# 4.net
KiCad netlist of a schematic drawn in EasyEDA Pro
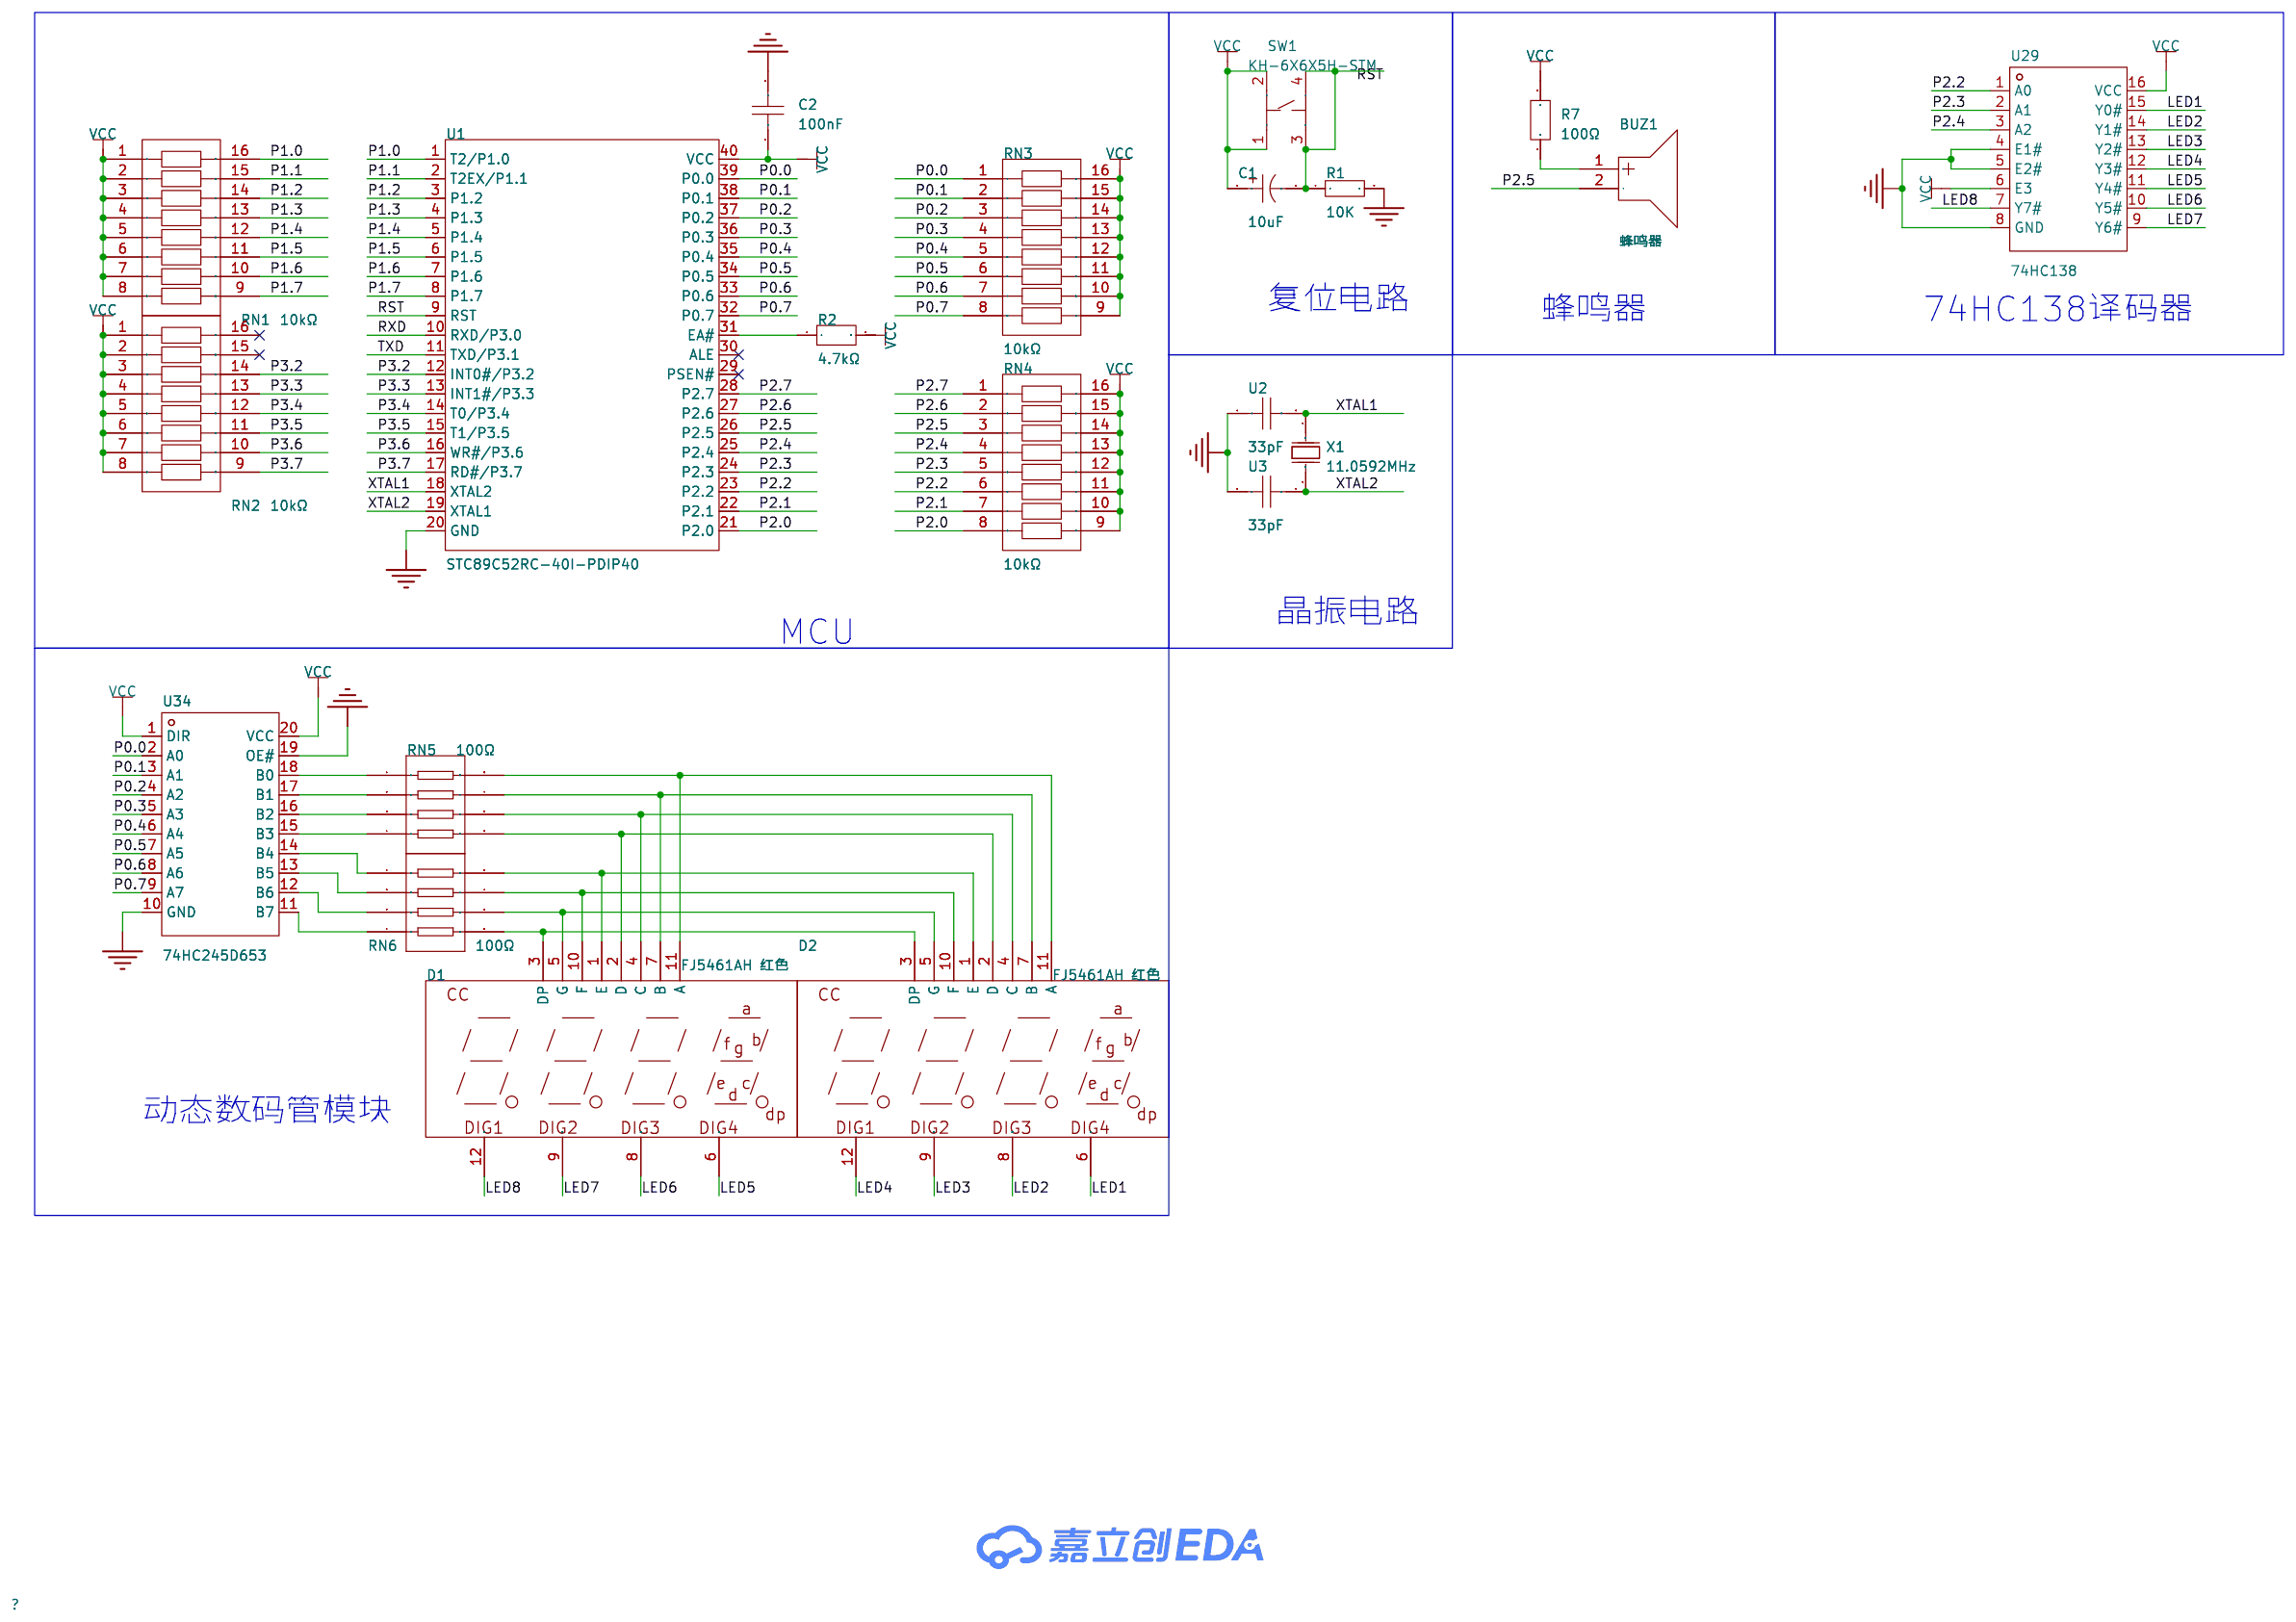
[diagram p0: schematic sheet]

(export (version "E")
  (design (tool "Eeschema 10.0.6"))
  (components
    (comp (ref "BUZ1")
      (value "蜂鸣器")
      (footprint "easyedapro:BUZ-TH_BD9.0-P5.00-D0.6-FD")
      (libsource (lib "easyedapro") (part "蜂鸣器"))
    )
    (comp (ref "C1")
      (value "10uF")
      (footprint "easyedapro:CAP-TH_BD10.0-P5.00-D0.6-FD_1")
      (description "容值:10uF;精度:±20%;额定电压:450V;纹波电流:200mA@100kHz;等效串联电阻(ESR):9Ω@100kHz;")
      (fields (field (name "Manufacturer Part") "CV100MPA16B") (field (name "Manufacturer") "TWBOR(伯鸿)"))
      (libsource (lib "easyedapro") (part "CV100MPA16B"))
    )
    (comp (ref "C2")
      (value "100nF")
      (footprint "easyedapro:C0603")
      (description "容值:100nF;精度:±10%;额定电压:25V;温度系数:X7R;")
      (fields
        (field (name "Manufacturer Part") "0603X7R104K250NT")
        (field (name "Manufacturer") "AIDE(爱迪电容)")
      )
      (libsource (lib "easyedapro") (part "0603X7R104K250NT"))
    )
    (comp (ref "D1")
      (value "FJ5461AH 红色")
      (footprint "easyedapro:LED-SEG-TH_FJ5461AH")
      (description "数码管位数:4位;功耗:-;发光颜色:红色;LED极性:共阴极;数字/字母大小(英寸):0.56;")
      (fields (field (name "Manufacturer") "志浩"))
      (libsource (lib "easyedapro") (part "FJ5461AH red"))
    )
    (comp (ref "D2")
      (value "FJ5461AH 红色")
      (footprint "easyedapro:LED-SEG-TH_FJ5461AH")
      (description "数码管位数:4位;功耗:-;发光颜色:红色;LED极性:共阴极;数字/字母大小(英寸):0.56;")
      (fields (field (name "Manufacturer") "志浩"))
      (libsource (lib "easyedapro") (part "FJ5461AH red"))
    )
    (comp (ref "R1") (value "10K") (footprint "easyedapro:R0603") (libsource (lib "easyedapro") (part "电阻")))
    (comp (ref "R2")
      (value "4.7kΩ")
      (footprint "easyedapro:R0805")
      (description "电阻类型:厚膜电阻;阻值:4.7kΩ;精度:±1%;功率:125mW;工作电压:-;温度系数:±100ppm/°C;")
      (fields
        (field (name "Manufacturer Part") "ERJ-U06F4701V")
        (field (name "Manufacturer") "PANASONIC(松下)")
      )
      (libsource (lib "easyedapro") (part "ERJ-U06F4701V"))
    )
    (comp (ref "R7")
      (value "100Ω")
      (footprint "easyedapro:R1206")
      (description "电阻类型:-;阻值:100Ω;精度:±5%;功率:250mW;工作电压:200V;")
      (fields
        (field (name "Manufacturer Part") "CQ06W4J0101T5E")
        (field (name "Manufacturer") "UNI-ROYAL(厚声)")
      )
      (libsource (lib "easyedapro") (part "CQ06W4J0101T5E"))
    )
    (comp (ref "RN1")
      (value "10kΩ")
      (footprint "easyedapro:DIP-16_L22.0-W6.7-P2.54-LS7.6-BL")
      (description "电阻器数:8;阻值:10kΩ;精度:±2%;单个元件功率:250mW;温度系数:±100ppm/°C;")
      (fields (field (name "Manufacturer Part") "4116R-1-103LF") (field (name "Manufacturer") "BOURNS"))
      (libsource (lib "easyedapro") (part "4116R-1-103LF"))
    )
    (comp (ref "RN2")
      (value "10kΩ")
      (footprint "easyedapro:DIP-16_L22.0-W6.7-P2.54-LS7.6-BL")
      (description "电阻器数:8;阻值:10kΩ;精度:±2%;单个元件功率:250mW;温度系数:±100ppm/°C;")
      (fields (field (name "Manufacturer Part") "4116R-1-103LF") (field (name "Manufacturer") "BOURNS"))
      (libsource (lib "easyedapro") (part "4116R-1-103LF"))
    )
    (comp (ref "RN3")
      (value "10kΩ")
      (footprint "easyedapro:DIP-16_L22.0-W6.7-P2.54-LS7.6-BL")
      (description "电阻器数:8;阻值:10kΩ;精度:±2%;单个元件功率:250mW;温度系数:±100ppm/°C;")
      (fields (field (name "Manufacturer Part") "4116R-1-103LF") (field (name "Manufacturer") "BOURNS"))
      (libsource (lib "easyedapro") (part "4116R-1-103LF"))
    )
    (comp (ref "RN4")
      (value "10kΩ")
      (footprint "easyedapro:DIP-16_L22.0-W6.7-P2.54-LS7.6-BL")
      (description "电阻器数:8;阻值:10kΩ;精度:±2%;单个元件功率:250mW;温度系数:±100ppm/°C;")
      (fields (field (name "Manufacturer Part") "4116R-1-103LF") (field (name "Manufacturer") "BOURNS"))
      (libsource (lib "easyedapro") (part "4116R-1-103LF"))
    )
    (comp (ref "RN5")
      (value "100Ω")
      (footprint "easyedapro:RES-ARRAY-SMD_0402-8P-L2.0-W1.0-BL")
      (description "电阻器数:4;阻值:100Ω;精度:±5%;单个元件功率:62.5mW;温度系数:±200ppm/°C;")
      (fields
        (field (name "Manufacturer Part") "4D02WGJ0101TCE")
        (field (name "Manufacturer") "UNI-ROYAL(厚声)")
      )
      (libsource (lib "easyedapro") (part "4D02WGJ0101TCE"))
    )
    (comp (ref "RN6")
      (value "100Ω")
      (footprint "easyedapro:RES-ARRAY-SMD_0402-8P-L2.0-W1.0-BL")
      (description "电阻器数:4;阻值:100Ω;精度:±5%;单个元件功率:62.5mW;温度系数:±200ppm/°C;")
      (fields
        (field (name "Manufacturer Part") "4D02WGJ0101TCE")
        (field (name "Manufacturer") "UNI-ROYAL(厚声)")
      )
      (libsource (lib "easyedapro") (part "4D02WGJ0101TCE"))
    )
    (comp (ref "SW1")
      (value "KH-6X6X5H-STM")
      (footprint "easyedapro:SW-SMD_4P-L6.0-W6.0-P4.50-LS9.0_H5.0")
      (description "电路结构:单刀单掷;按钮形状:圆形按钮;安装方式:立贴;开关长度:6mm;开关宽度:6mm;开关高度:5mm;带支架:不带;触点电流:50mA;额定电压(DC):12V;机械寿命:8万次;")
      (fields (field (name "Manufacturer") "kinghelm(金航标)"))
      (libsource (lib "easyedapro") (part "KH-6X6X5H-STM"))
    )
    (comp (ref "U1")
      (value "STC89C52RC-40I-PDIP40")
      (footprint "easyedapro:DIP-40_L52.0-W13.7-P2.54-LS15.2-BL")
      (description "CPU内核:51系列;应用领域:-;")
      (fields (field (name "Manufacturer") "STC"))
      (libsource (lib "easyedapro") (part "STC89C52RC-40I"))
    )
    (comp (ref "U2")
      (value "33pF")
      (footprint "easyedapro:C0603")
      (description "容值:33pF;精度:±1%;额定电压:50V;温度系数:-;")
      (fields
        (field (name "Manufacturer Part") "GRM1885C1H330FA01D")
        (field (name "Manufacturer") "muRata(村田)")
      )
      (libsource (lib "easyedapro") (part "GRM1885C1H330FA01D"))
    )
    (comp (ref "U3")
      (value "33pF")
      (footprint "easyedapro:C0603")
      (description "容值:33pF;精度:±1%;额定电压:50V;温度系数:-;")
      (fields
        (field (name "Manufacturer Part") "GRM1885C1H330FA01D")
        (field (name "Manufacturer") "muRata(村田)")
      )
      (libsource (lib "easyedapro") (part "GRM1885C1H330FA01D"))
    )
    (comp (ref "U29")
      (value "74HC138")
      (footprint "easyedapro:SOIC-16_L9.9-W3.9-P1.27-LS6.0-BL")
      (description "三八译码器，74系列逻辑芯片,2.0V-6.0V供电电压。")
      (fields (field (name "Manufacturer") "FM(富满)"))
      (libsource (lib "easyedapro") (part "74HC138"))
    )
    (comp (ref "U34")
      (value "74HC245D653")
      (footprint "easyedapro:SOIC-20_L13.0-W7.6-P1.27-LS10.3-BL")
      (libsource (lib "easyedapro") (part "74HC245D653"))
    )
    (comp (ref "X1")
      (value "11.0592MHz")
      (footprint "easyedapro:HC-49US_L11.5-W4.5-P4.88")
      (description "晶振类型:直插晶振;频率:11.0592MHz;常温频差:±20ppm;负载电容:20pF;频率稳定度:±30ppm;")
      (fields
        (field (name "Manufacturer Part") "X49SD110592MSD2SC")
        (field (name "Manufacturer") "YXC(扬兴晶振)")
      )
      (libsource (lib "easyedapro") (part "X49SD110592MSD2SC"))
    )
  )
  (nets
    (net (code "1") (name "/LED1") (class "Default")
      (node (ref "D2") (pin "6") (pinfunction "DIG4_6") (pintype "input"))
      (node (ref "U29") (pin "15") (pinfunction "Y0#_15") (pintype "unspecified"))
    )
    (net (code "2") (name "/LED2") (class "Default")
      (node (ref "D2") (pin "8") (pinfunction "DIG3_8") (pintype "input"))
      (node (ref "U29") (pin "14") (pinfunction "Y1#_14") (pintype "unspecified"))
    )
    (net (code "3") (name "/LED3") (class "Default")
      (node (ref "D2") (pin "9") (pinfunction "DIG2_9") (pintype "input"))
      (node (ref "U29") (pin "13") (pinfunction "Y2#_13") (pintype "unspecified"))
    )
    (net (code "4") (name "/LED4") (class "Default")
      (node (ref "D2") (pin "12") (pinfunction "DIG1_12") (pintype "input"))
      (node (ref "U29") (pin "12") (pinfunction "Y3#_12") (pintype "unspecified"))
    )
    (net (code "5") (name "/LED5") (class "Default")
      (node (ref "D1") (pin "6") (pinfunction "DIG4_6") (pintype "input"))
      (node (ref "U29") (pin "11") (pinfunction "Y4#_11") (pintype "unspecified"))
    )
    (net (code "6") (name "/LED6") (class "Default")
      (node (ref "D1") (pin "8") (pinfunction "DIG3_8") (pintype "input"))
      (node (ref "U29") (pin "10") (pinfunction "Y5#_10") (pintype "unspecified"))
    )
    (net (code "7") (name "/LED7") (class "Default")
      (node (ref "D1") (pin "9") (pinfunction "DIG2_9") (pintype "input"))
      (node (ref "U29") (pin "9") (pinfunction "Y6#_9") (pintype "unspecified"))
    )
    (net (code "8") (name "/LED8") (class "Default")
      (node (ref "D1") (pin "12") (pinfunction "DIG1_12") (pintype "input"))
      (node (ref "U29") (pin "7") (pinfunction "Y7#_7") (pintype "unspecified"))
    )
    (net (code "9") (name "/P0.0") (class "Default")
      (node (ref "RN3") (pin "1") (pinfunction "1_1") (pintype "unspecified"))
      (node (ref "U1") (pin "39") (pinfunction "P0.0_39") (pintype "unspecified"))
      (node (ref "U34") (pin "2") (pinfunction "A0_2") (pintype "unspecified"))
    )
    (net (code "10") (name "/P0.1") (class "Default")
      (node (ref "RN3") (pin "2") (pinfunction "2_2") (pintype "unspecified"))
      (node (ref "U1") (pin "38") (pinfunction "P0.1_38") (pintype "unspecified"))
      (node (ref "U34") (pin "3") (pinfunction "A1_3") (pintype "unspecified"))
    )
    (net (code "11") (name "/P0.2") (class "Default")
      (node (ref "RN3") (pin "3") (pinfunction "3_3") (pintype "unspecified"))
      (node (ref "U1") (pin "37") (pinfunction "P0.2_37") (pintype "unspecified"))
      (node (ref "U34") (pin "4") (pinfunction "A2_4") (pintype "unspecified"))
    )
    (net (code "12") (name "/P0.3") (class "Default")
      (node (ref "RN3") (pin "4") (pinfunction "4_4") (pintype "unspecified"))
      (node (ref "U1") (pin "36") (pinfunction "P0.3_36") (pintype "unspecified"))
      (node (ref "U34") (pin "5") (pinfunction "A3_5") (pintype "unspecified"))
    )
    (net (code "13") (name "/P0.4") (class "Default")
      (node (ref "RN3") (pin "5") (pinfunction "5_5") (pintype "unspecified"))
      (node (ref "U1") (pin "35") (pinfunction "P0.4_35") (pintype "unspecified"))
      (node (ref "U34") (pin "6") (pinfunction "A4_6") (pintype "unspecified"))
    )
    (net (code "14") (name "/P0.5") (class "Default")
      (node (ref "RN3") (pin "6") (pinfunction "6_6") (pintype "unspecified"))
      (node (ref "U1") (pin "34") (pinfunction "P0.5_34") (pintype "unspecified"))
      (node (ref "U34") (pin "7") (pinfunction "A5_7") (pintype "unspecified"))
    )
    (net (code "15") (name "/P0.6") (class "Default")
      (node (ref "RN3") (pin "7") (pinfunction "7_7") (pintype "unspecified"))
      (node (ref "U1") (pin "33") (pinfunction "P0.6_33") (pintype "unspecified"))
      (node (ref "U34") (pin "8") (pinfunction "A6_8") (pintype "unspecified"))
    )
    (net (code "16") (name "/P0.7") (class "Default")
      (node (ref "RN3") (pin "8") (pinfunction "8_8") (pintype "unspecified"))
      (node (ref "U1") (pin "32") (pinfunction "P0.7_32") (pintype "unspecified"))
      (node (ref "U34") (pin "9") (pinfunction "A7_9") (pintype "unspecified"))
    )
    (net (code "17") (name "/P1.0") (class "Default")
      (node (ref "RN1") (pin "16") (pinfunction "16_16") (pintype "unspecified"))
      (node (ref "U1") (pin "1") (pinfunction "T2/P1.0_1") (pintype "unspecified"))
    )
    (net (code "18") (name "/P1.1") (class "Default")
      (node (ref "RN1") (pin "15") (pinfunction "15_15") (pintype "unspecified"))
      (node (ref "U1") (pin "2") (pinfunction "T2EX/P1.1_2") (pintype "unspecified"))
    )
    (net (code "19") (name "/P1.2") (class "Default")
      (node (ref "RN1") (pin "14") (pinfunction "14_14") (pintype "unspecified"))
      (node (ref "U1") (pin "3") (pinfunction "P1.2_3") (pintype "unspecified"))
    )
    (net (code "20") (name "/P1.3") (class "Default")
      (node (ref "RN1") (pin "13") (pinfunction "13_13") (pintype "unspecified"))
      (node (ref "U1") (pin "4") (pinfunction "P1.3_4") (pintype "unspecified"))
    )
    (net (code "21") (name "/P1.4") (class "Default")
      (node (ref "RN1") (pin "12") (pinfunction "12_12") (pintype "unspecified"))
      (node (ref "U1") (pin "5") (pinfunction "P1.4_5") (pintype "unspecified"))
    )
    (net (code "22") (name "/P1.5") (class "Default")
      (node (ref "RN1") (pin "11") (pinfunction "11_11") (pintype "unspecified"))
      (node (ref "U1") (pin "6") (pinfunction "P1.5_6") (pintype "unspecified"))
    )
    (net (code "23") (name "/P1.6") (class "Default")
      (node (ref "RN1") (pin "10") (pinfunction "10_10") (pintype "unspecified"))
      (node (ref "U1") (pin "7") (pinfunction "P1.6_7") (pintype "unspecified"))
    )
    (net (code "24") (name "/P1.7") (class "Default")
      (node (ref "RN1") (pin "9") (pinfunction "9_9") (pintype "unspecified"))
      (node (ref "U1") (pin "8") (pinfunction "P1.7_8") (pintype "unspecified"))
    )
    (net (code "25") (name "/P2.0") (class "Default")
      (node (ref "RN4") (pin "8") (pinfunction "8_8") (pintype "unspecified"))
      (node (ref "U1") (pin "21") (pinfunction "P2.0_21") (pintype "unspecified"))
    )
    (net (code "26") (name "/P2.1") (class "Default")
      (node (ref "RN4") (pin "7") (pinfunction "7_7") (pintype "unspecified"))
      (node (ref "U1") (pin "22") (pinfunction "P2.1_22") (pintype "unspecified"))
    )
    (net (code "27") (name "/P2.2") (class "Default")
      (node (ref "RN4") (pin "6") (pinfunction "6_6") (pintype "unspecified"))
      (node (ref "U1") (pin "23") (pinfunction "P2.2_23") (pintype "unspecified"))
      (node (ref "U29") (pin "1") (pinfunction "A0_1") (pintype "unspecified"))
    )
    (net (code "28") (name "/P2.3") (class "Default")
      (node (ref "RN4") (pin "5") (pinfunction "5_5") (pintype "unspecified"))
      (node (ref "U1") (pin "24") (pinfunction "P2.3_24") (pintype "unspecified"))
      (node (ref "U29") (pin "2") (pinfunction "A1_2") (pintype "unspecified"))
    )
    (net (code "29") (name "/P2.4") (class "Default")
      (node (ref "RN4") (pin "4") (pinfunction "4_4") (pintype "unspecified"))
      (node (ref "U1") (pin "25") (pinfunction "P2.4_25") (pintype "unspecified"))
      (node (ref "U29") (pin "3") (pinfunction "A2_3") (pintype "unspecified"))
    )
    (net (code "30") (name "/P2.5") (class "Default")
      (node (ref "BUZ1") (pin "2") (pinfunction "-_2") (pintype "unspecified"))
      (node (ref "RN4") (pin "3") (pinfunction "3_3") (pintype "unspecified"))
      (node (ref "U1") (pin "26") (pinfunction "P2.5_26") (pintype "unspecified"))
    )
    (net (code "31") (name "/P2.6") (class "Default")
      (node (ref "RN4") (pin "2") (pinfunction "2_2") (pintype "unspecified"))
      (node (ref "U1") (pin "27") (pinfunction "P2.6_27") (pintype "unspecified"))
    )
    (net (code "32") (name "/P2.7") (class "Default")
      (node (ref "RN4") (pin "1") (pinfunction "1_1") (pintype "unspecified"))
      (node (ref "U1") (pin "28") (pinfunction "P2.7_28") (pintype "unspecified"))
    )
    (net (code "33") (name "/P3.2") (class "Default")
      (node (ref "RN2") (pin "14") (pinfunction "14_14") (pintype "unspecified"))
      (node (ref "U1") (pin "12") (pinfunction "INT0#/P3.2_12") (pintype "unspecified"))
    )
    (net (code "34") (name "/P3.3") (class "Default")
      (node (ref "RN2") (pin "13") (pinfunction "13_13") (pintype "unspecified"))
      (node (ref "U1") (pin "13") (pinfunction "INT1#/P3.3_13") (pintype "unspecified"))
    )
    (net (code "35") (name "/P3.4") (class "Default")
      (node (ref "RN2") (pin "12") (pinfunction "12_12") (pintype "unspecified"))
      (node (ref "U1") (pin "14") (pinfunction "T0/P3.4_14") (pintype "unspecified"))
    )
    (net (code "36") (name "/P3.5") (class "Default")
      (node (ref "RN2") (pin "11") (pinfunction "11_11") (pintype "unspecified"))
      (node (ref "U1") (pin "15") (pinfunction "T1/P3.5_15") (pintype "unspecified"))
    )
    (net (code "37") (name "/P3.6") (class "Default")
      (node (ref "RN2") (pin "10") (pinfunction "10_10") (pintype "unspecified"))
      (node (ref "U1") (pin "16") (pinfunction "WR#/P3.6_16") (pintype "unspecified"))
    )
    (net (code "38") (name "/P3.7") (class "Default")
      (node (ref "RN2") (pin "9") (pinfunction "9_9") (pintype "unspecified"))
      (node (ref "U1") (pin "17") (pinfunction "RD#/P3.7_17") (pintype "unspecified"))
    )
    (net (code "39") (name "/RST") (class "Default")
      (node (ref "C1") (pin "2") (pinfunction "2_2") (pintype "input"))
      (node (ref "R1") (pin "1") (pinfunction "1_1") (pintype "input"))
      (node (ref "SW1") (pin "3") (pinfunction "3_3") (pintype "unspecified"))
      (node (ref "SW1") (pin "4") (pinfunction "4_4") (pintype "unspecified"))
      (node (ref "U1") (pin "9") (pinfunction "RST_9") (pintype "unspecified"))
    )
    (net (code "40") (name "/RXD") (class "Default")
      (node (ref "U1") (pin "10") (pinfunction "RXD/P3.0_10") (pintype "unspecified"))
    )
    (net (code "41") (name "/TXD") (class "Default")
      (node (ref "U1") (pin "11") (pinfunction "TXD/P3.1_11") (pintype "unspecified"))
    )
    (net (code "42") (name "/XTAL1") (class "Default")
      (node (ref "U1") (pin "18") (pinfunction "XTAL2_18") (pintype "unspecified"))
      (node (ref "U2") (pin "2") (pinfunction "2_2") (pintype "unspecified"))
      (node (ref "X1") (pin "1") (pinfunction "OSC1_1") (pintype "input"))
    )
    (net (code "43") (name "/XTAL2") (class "Default")
      (node (ref "U1") (pin "19") (pinfunction "XTAL1_19") (pintype "unspecified"))
      (node (ref "U3") (pin "1") (pinfunction "1_1") (pintype "unspecified"))
      (node (ref "X1") (pin "2") (pinfunction "OSC2_2") (pintype "input"))
    )
    (net (code "44") (name "GND") (class "Default")
      (node (ref "C2") (pin "2") (pinfunction "2_2") (pintype "unspecified"))
      (node (ref "R1") (pin "2") (pinfunction "2_2") (pintype "input"))
      (node (ref "U1") (pin "20") (pinfunction "GND_20") (pintype "unspecified"))
      (node (ref "U2") (pin "1") (pinfunction "1_1") (pintype "unspecified"))
      (node (ref "U29") (pin "4") (pinfunction "E1#_4") (pintype "unspecified"))
      (node (ref "U29") (pin "5") (pinfunction "E2#_5") (pintype "unspecified"))
      (node (ref "U29") (pin "8") (pinfunction "GND_8") (pintype "unspecified"))
      (node (ref "U3") (pin "2") (pinfunction "2_2") (pintype "unspecified"))
      (node (ref "U34") (pin "10") (pinfunction "GND_10") (pintype "unspecified"))
      (node (ref "U34") (pin "19") (pinfunction "OE#_19") (pintype "unspecified"))
    )
    (net (code "45") (name "Net-(BUZ1-+)") (class "Default")
      (node (ref "BUZ1") (pin "1") (pinfunction "+_1") (pintype "unspecified"))
      (node (ref "R7") (pin "1") (pinfunction "1_1") (pintype "unspecified"))
    )
    (net (code "46") (name "Net-(D1-A)") (class "Default")
      (node (ref "D1") (pin "11") (pinfunction "A_11") (pintype "input"))
      (node (ref "D2") (pin "11") (pinfunction "A_11") (pintype "input"))
      (node (ref "RN5") (pin "8") (pinfunction "8_8") (pintype "input"))
    )
    (net (code "47") (name "Net-(D1-B)") (class "Default")
      (node (ref "D1") (pin "7") (pinfunction "B_7") (pintype "input"))
      (node (ref "D2") (pin "7") (pinfunction "B_7") (pintype "input"))
      (node (ref "RN5") (pin "7") (pinfunction "7_7") (pintype "input"))
    )
    (net (code "48") (name "Net-(D1-C)") (class "Default")
      (node (ref "D1") (pin "4") (pinfunction "C_4") (pintype "input"))
      (node (ref "D2") (pin "4") (pinfunction "C_4") (pintype "input"))
      (node (ref "RN5") (pin "6") (pinfunction "6_6") (pintype "input"))
    )
    (net (code "49") (name "Net-(D1-D)") (class "Default")
      (node (ref "D1") (pin "2") (pinfunction "D_2") (pintype "input"))
      (node (ref "D2") (pin "2") (pinfunction "D_2") (pintype "input"))
      (node (ref "RN5") (pin "5") (pinfunction "5_5") (pintype "input"))
    )
    (net (code "50") (name "Net-(D1-DP)") (class "Default")
      (node (ref "D1") (pin "3") (pinfunction "DP_3") (pintype "input"))
      (node (ref "D2") (pin "3") (pinfunction "DP_3") (pintype "input"))
      (node (ref "RN6") (pin "5") (pinfunction "5_5") (pintype "input"))
    )
    (net (code "51") (name "Net-(D1-E)") (class "Default")
      (node (ref "D1") (pin "1") (pinfunction "E_1") (pintype "input"))
      (node (ref "D2") (pin "1") (pinfunction "E_1") (pintype "input"))
      (node (ref "RN6") (pin "8") (pinfunction "8_8") (pintype "input"))
    )
    (net (code "52") (name "Net-(D1-F)") (class "Default")
      (node (ref "D1") (pin "10") (pinfunction "F_10") (pintype "input"))
      (node (ref "D2") (pin "10") (pinfunction "F_10") (pintype "input"))
      (node (ref "RN6") (pin "7") (pinfunction "7_7") (pintype "input"))
    )
    (net (code "53") (name "Net-(D1-G)") (class "Default")
      (node (ref "D1") (pin "5") (pinfunction "G_5") (pintype "input"))
      (node (ref "D2") (pin "5") (pinfunction "G_5") (pintype "input"))
      (node (ref "RN6") (pin "6") (pinfunction "6_6") (pintype "input"))
    )
    (net (code "54") (name "Net-(U1-EA#)") (class "Default")
      (node (ref "R2") (pin "1") (pinfunction "1_1") (pintype "unspecified"))
      (node (ref "U1") (pin "31") (pinfunction "EA#_31") (pintype "unspecified"))
    )
    (net (code "55") (name "Net-(U34-B0)") (class "Default")
      (node (ref "RN5") (pin "1") (pinfunction "1_1") (pintype "input"))
      (node (ref "U34") (pin "18") (pinfunction "B0_18") (pintype "unspecified"))
    )
    (net (code "56") (name "Net-(U34-B1)") (class "Default")
      (node (ref "RN5") (pin "2") (pinfunction "2_2") (pintype "input"))
      (node (ref "U34") (pin "17") (pinfunction "B1_17") (pintype "unspecified"))
    )
    (net (code "57") (name "Net-(U34-B2)") (class "Default")
      (node (ref "RN5") (pin "3") (pinfunction "3_3") (pintype "input"))
      (node (ref "U34") (pin "16") (pinfunction "B2_16") (pintype "unspecified"))
    )
    (net (code "58") (name "Net-(U34-B3)") (class "Default")
      (node (ref "RN5") (pin "4") (pinfunction "4_4") (pintype "input"))
      (node (ref "U34") (pin "15") (pinfunction "B3_15") (pintype "unspecified"))
    )
    (net (code "59") (name "Net-(U34-B4)") (class "Default")
      (node (ref "RN6") (pin "1") (pinfunction "1_1") (pintype "input"))
      (node (ref "U34") (pin "14") (pinfunction "B4_14") (pintype "unspecified"))
    )
    (net (code "60") (name "Net-(U34-B5)") (class "Default")
      (node (ref "RN6") (pin "2") (pinfunction "2_2") (pintype "input"))
      (node (ref "U34") (pin "13") (pinfunction "B5_13") (pintype "unspecified"))
    )
    (net (code "61") (name "Net-(U34-B6)") (class "Default")
      (node (ref "RN6") (pin "3") (pinfunction "3_3") (pintype "input"))
      (node (ref "U34") (pin "12") (pinfunction "B6_12") (pintype "unspecified"))
    )
    (net (code "62") (name "Net-(U34-B7)") (class "Default")
      (node (ref "RN6") (pin "4") (pinfunction "4_4") (pintype "input"))
      (node (ref "U34") (pin "11") (pinfunction "B7_11") (pintype "unspecified"))
    )
    (net (code "63") (name "VCC") (class "Default")
      (node (ref "C1") (pin "1") (pinfunction "1_1") (pintype "input"))
      (node (ref "C2") (pin "1") (pinfunction "1_1") (pintype "unspecified"))
      (node (ref "R2") (pin "2") (pinfunction "2_2") (pintype "unspecified"))
      (node (ref "R7") (pin "2") (pinfunction "2_2") (pintype "unspecified"))
      (node (ref "RN1") (pin "1") (pinfunction "1_1") (pintype "unspecified"))
      (node (ref "RN1") (pin "2") (pinfunction "2_2") (pintype "unspecified"))
      (node (ref "RN1") (pin "3") (pinfunction "3_3") (pintype "unspecified"))
      (node (ref "RN1") (pin "4") (pinfunction "4_4") (pintype "unspecified"))
      (node (ref "RN1") (pin "5") (pinfunction "5_5") (pintype "unspecified"))
      (node (ref "RN1") (pin "6") (pinfunction "6_6") (pintype "unspecified"))
      (node (ref "RN1") (pin "7") (pinfunction "7_7") (pintype "unspecified"))
      (node (ref "RN1") (pin "8") (pinfunction "8_8") (pintype "unspecified"))
      (node (ref "RN2") (pin "1") (pinfunction "1_1") (pintype "unspecified"))
      (node (ref "RN2") (pin "2") (pinfunction "2_2") (pintype "unspecified"))
      (node (ref "RN2") (pin "3") (pinfunction "3_3") (pintype "unspecified"))
      (node (ref "RN2") (pin "4") (pinfunction "4_4") (pintype "unspecified"))
      (node (ref "RN2") (pin "5") (pinfunction "5_5") (pintype "unspecified"))
      (node (ref "RN2") (pin "6") (pinfunction "6_6") (pintype "unspecified"))
      (node (ref "RN2") (pin "7") (pinfunction "7_7") (pintype "unspecified"))
      (node (ref "RN2") (pin "8") (pinfunction "8_8") (pintype "unspecified"))
      (node (ref "RN3") (pin "10") (pinfunction "10_10") (pintype "unspecified"))
      (node (ref "RN3") (pin "11") (pinfunction "11_11") (pintype "unspecified"))
      (node (ref "RN3") (pin "12") (pinfunction "12_12") (pintype "unspecified"))
      (node (ref "RN3") (pin "13") (pinfunction "13_13") (pintype "unspecified"))
      (node (ref "RN3") (pin "14") (pinfunction "14_14") (pintype "unspecified"))
      (node (ref "RN3") (pin "15") (pinfunction "15_15") (pintype "unspecified"))
      (node (ref "RN3") (pin "16") (pinfunction "16_16") (pintype "unspecified"))
      (node (ref "RN3") (pin "9") (pinfunction "9_9") (pintype "unspecified"))
      (node (ref "RN4") (pin "10") (pinfunction "10_10") (pintype "unspecified"))
      (node (ref "RN4") (pin "11") (pinfunction "11_11") (pintype "unspecified"))
      (node (ref "RN4") (pin "12") (pinfunction "12_12") (pintype "unspecified"))
      (node (ref "RN4") (pin "13") (pinfunction "13_13") (pintype "unspecified"))
      (node (ref "RN4") (pin "14") (pinfunction "14_14") (pintype "unspecified"))
      (node (ref "RN4") (pin "15") (pinfunction "15_15") (pintype "unspecified"))
      (node (ref "RN4") (pin "16") (pinfunction "16_16") (pintype "unspecified"))
      (node (ref "RN4") (pin "9") (pinfunction "9_9") (pintype "unspecified"))
      (node (ref "SW1") (pin "1") (pinfunction "1_1") (pintype "unspecified"))
      (node (ref "SW1") (pin "2") (pinfunction "2_2") (pintype "unspecified"))
      (node (ref "U1") (pin "40") (pinfunction "VCC_40") (pintype "unspecified"))
      (node (ref "U29") (pin "16") (pinfunction "VCC_16") (pintype "unspecified"))
      (node (ref "U29") (pin "6") (pinfunction "E3_6") (pintype "unspecified"))
      (node (ref "U34") (pin "1") (pinfunction "DIR_1") (pintype "unspecified"))
      (node (ref "U34") (pin "20") (pinfunction "VCC_20") (pintype "unspecified"))
    )
    (net (code "64") (name "unconnected-(RN2-Pad15)") (class "Default")
      (node (ref "RN2") (pin "15") (pinfunction "15_15") (pintype "unspecified+no_connect"))
    )
    (net (code "65") (name "unconnected-(RN2-Pad16)") (class "Default")
      (node (ref "RN2") (pin "16") (pinfunction "16_16") (pintype "unspecified+no_connect"))
    )
    (net (code "66") (name "unconnected-(U1-ALE-Pad30)") (class "Default")
      (node (ref "U1") (pin "30") (pinfunction "ALE_30") (pintype "unspecified+no_connect"))
    )
    (net (code "67") (name "unconnected-(U1-PSEN#-Pad29)") (class "Default")
      (node (ref "U1") (pin "29") (pinfunction "PSEN#_29") (pintype "unspecified+no_connect"))
    )
  )
)
